# energy_counter_rfm70.net
KiCad netlist of a schematic drawn in EAGLE
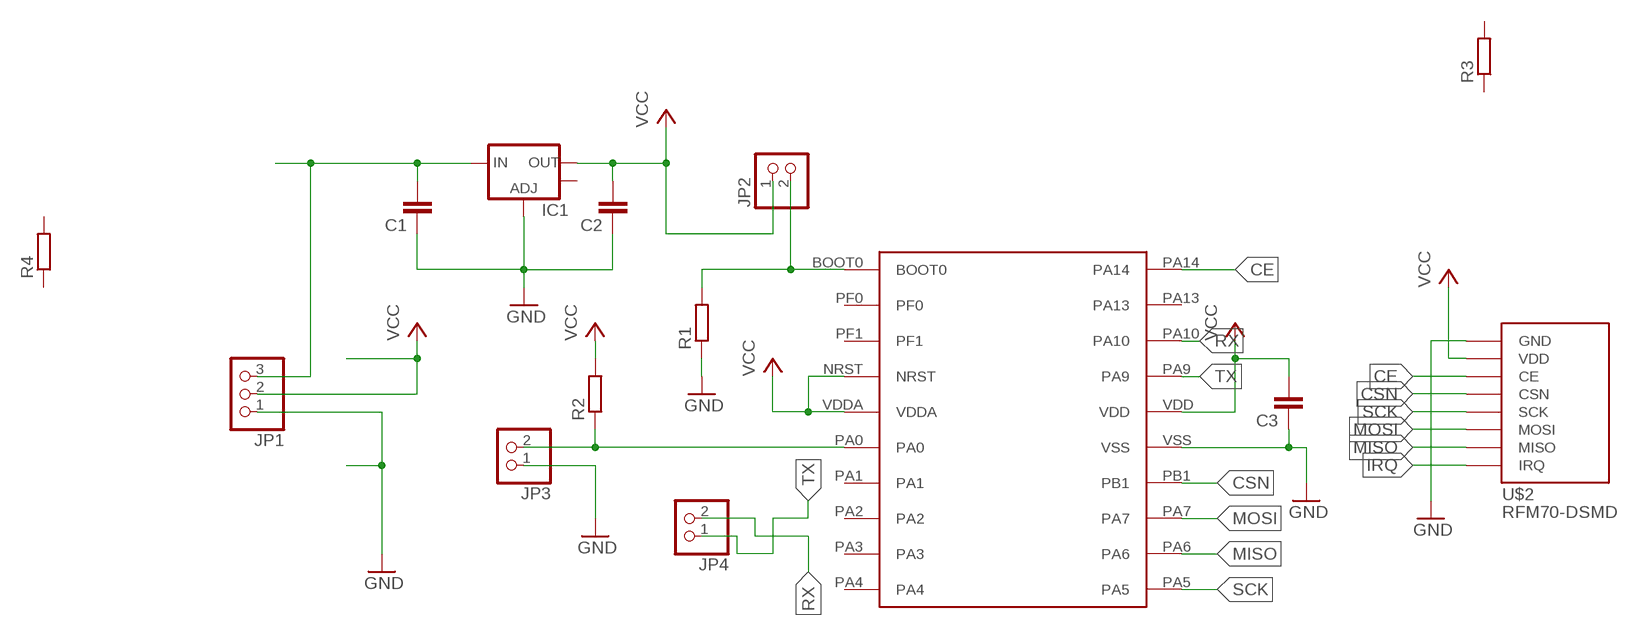
[diagram p0: schematic, sheet 1]

(export (version "E")
  (design (tool "Eeschema 10.0.6"))
  (components
    (comp (ref "C1")
      (value "C-EUC1206")
      (footprint "eagle-import:C1206")
      (libsource (lib "eagle-import") (part "C-EUC1206"))
    )
    (comp (ref "C2")
      (value "C-EUC0805")
      (footprint "eagle-import:C0805")
      (libsource (lib "eagle-import") (part "C-EUC0805"))
    )
    (comp (ref "C3")
      (value "C-EUC0805")
      (footprint "eagle-import:C0805")
      (libsource (lib "eagle-import") (part "C-EUC0805"))
    )
    (comp (ref "IC1")
      (value "V_REG_LM1117SOT223")
      (footprint "eagle-import:SOT223")
      (libsource (lib "eagle-import") (part "V_REG_LM1117SOT223"))
    )
    (comp (ref "JP1")
      (value "PINHD-1X3/90")
      (footprint "eagle-import:1X03_90")
      (libsource (lib "eagle-import") (part "PINHD-1X3/90"))
    )
    (comp (ref "JP2")
      (value "PINHD-1X2/90")
      (footprint "eagle-import:1X02_90")
      (libsource (lib "eagle-import") (part "PINHD-1X2/90"))
    )
    (comp (ref "JP3")
      (value "PINHD-1X2/90")
      (footprint "eagle-import:1X02_90")
      (libsource (lib "eagle-import") (part "PINHD-1X2/90"))
    )
    (comp (ref "JP4")
      (value "PINHD-1X2/90")
      (footprint "eagle-import:1X02_90")
      (libsource (lib "eagle-import") (part "PINHD-1X2/90"))
    )
    (comp (ref "R1")
      (value "R-EU_R1206")
      (footprint "eagle-import:R1206")
      (libsource (lib "eagle-import") (part "R-EU_R1206"))
    )
    (comp (ref "R2")
      (value "R-EU_R0805")
      (footprint "eagle-import:R0805")
      (libsource (lib "eagle-import") (part "R-EU_R0805"))
    )
    (comp (ref "R3")
      (value "R-EU_R1206")
      (footprint "eagle-import:R1206")
      (libsource (lib "eagle-import") (part "R-EU_R1206"))
    )
    (comp (ref "R4")
      (value "R-EU_R1206")
      (footprint "eagle-import:R1206")
      (libsource (lib "eagle-import") (part "R-EU_R1206"))
    )
    (comp (ref "U$1")
      (value "STM32F0")
      (footprint "eagle-import:TSSOP20")
      (libsource (lib "eagle-import") (part "STM32F0"))
    )
    (comp (ref "U$2")
      (value "RFM70-DSMD")
      (footprint "eagle-import:RFM70-SMD")
      (libsource (lib "eagle-import") (part "RFM70-DSMD"))
    )
  )
  (nets
    (net (code "1") (name "CE") (class "Default")
      (node (ref "U$1") (pin "PA14") (pinfunction "PA14_PA14") (pintype "bidirectional"))
      (node (ref "U$2") (pin "CE") (pinfunction "CE_CE") (pintype "bidirectional"))
    )
    (net (code "2") (name "CSN") (class "Default")
      (node (ref "U$1") (pin "PB1") (pinfunction "PB1_PB1") (pintype "bidirectional"))
      (node (ref "U$2") (pin "CSN") (pinfunction "CSN_CSN") (pintype "bidirectional"))
    )
    (net (code "3") (name "GND") (class "Default")
      (node (ref "C1") (pin "1") (pinfunction "1_1") (pintype "passive"))
      (node (ref "C2") (pin "1") (pinfunction "1_1") (pintype "passive"))
      (node (ref "C3") (pin "1") (pinfunction "1_1") (pintype "passive"))
      (node (ref "IC1") (pin "1") (pinfunction "ADJ_1") (pintype "input"))
      (node (ref "JP1") (pin "1") (pinfunction "1_1") (pintype "passive"))
      (node (ref "JP3") (pin "1") (pinfunction "1_1") (pintype "passive"))
      (node (ref "R1") (pin "1") (pinfunction "1_1") (pintype "passive"))
      (node (ref "U$1") (pin "VSS") (pinfunction "VSS_VSS") (pintype "bidirectional"))
      (node (ref "U$2") (pin "GND") (pinfunction "GND_GND") (pintype "bidirectional"))
    )
    (net (code "4") (name "IRQ") (class "Default")
      (node (ref "U$2") (pin "IRQ") (pinfunction "IRQ_IRQ") (pintype "bidirectional"))
    )
    (net (code "5") (name "MISO") (class "Default")
      (node (ref "U$1") (pin "PA6") (pinfunction "PA6_PA6") (pintype "bidirectional"))
      (node (ref "U$2") (pin "MISO") (pinfunction "MISO_MISO") (pintype "bidirectional"))
    )
    (net (code "6") (name "MOSI") (class "Default")
      (node (ref "U$1") (pin "PA7") (pinfunction "PA7_PA7") (pintype "bidirectional"))
      (node (ref "U$2") (pin "MOSI") (pinfunction "MOSI_MOSI") (pintype "bidirectional"))
    )
    (net (code "7") (name "Net-(IC1-IN)") (class "Default")
      (node (ref "C1") (pin "2") (pinfunction "2_2") (pintype "passive"))
      (node (ref "IC1") (pin "3") (pinfunction "IN_3") (pintype "input"))
      (node (ref "JP1") (pin "3") (pinfunction "3_3") (pintype "passive"))
    )
    (net (code "8") (name "Net-(JP2-Pad2)") (class "Default")
      (node (ref "JP2") (pin "2") (pinfunction "2_2") (pintype "passive"))
      (node (ref "R1") (pin "2") (pinfunction "2_2") (pintype "passive"))
      (node (ref "U$1") (pin "BOOT0") (pinfunction "BOOT0_BOOT0") (pintype "bidirectional"))
    )
    (net (code "9") (name "Net-(JP3-Pad2)") (class "Default")
      (node (ref "JP3") (pin "2") (pinfunction "2_2") (pintype "passive"))
      (node (ref "R2") (pin "1") (pinfunction "1_1") (pintype "passive"))
      (node (ref "U$1") (pin "PA0") (pinfunction "PA0_PA0") (pintype "bidirectional"))
    )
    (net (code "10") (name "RX") (class "Default")
      (node (ref "JP4") (pin "2") (pinfunction "2_2") (pintype "passive"))
      (node (ref "U$1") (pin "PA10") (pinfunction "PA10_PA10") (pintype "bidirectional"))
    )
    (net (code "11") (name "SCK") (class "Default")
      (node (ref "U$1") (pin "PA5") (pinfunction "PA5_PA5") (pintype "bidirectional"))
      (node (ref "U$2") (pin "SCK") (pinfunction "SCK_SCK") (pintype "bidirectional"))
    )
    (net (code "12") (name "TX") (class "Default")
      (node (ref "JP4") (pin "1") (pinfunction "1_1") (pintype "passive"))
      (node (ref "U$1") (pin "PA9") (pinfunction "PA9_PA9") (pintype "bidirectional"))
    )
    (net (code "13") (name "VCC") (class "Default")
      (node (ref "C2") (pin "2") (pinfunction "2_2") (pintype "passive"))
      (node (ref "C3") (pin "2") (pinfunction "2_2") (pintype "passive"))
      (node (ref "IC1") (pin "2") (pinfunction "OUT_2") (pintype "output"))
      (node (ref "JP1") (pin "2") (pinfunction "2_2") (pintype "passive"))
      (node (ref "JP2") (pin "1") (pinfunction "1_1") (pintype "passive"))
      (node (ref "R2") (pin "2") (pinfunction "2_2") (pintype "passive"))
      (node (ref "U$1") (pin "NRST") (pinfunction "NRST_NRST") (pintype "bidirectional"))
      (node (ref "U$1") (pin "VDD") (pinfunction "VDD_VDD") (pintype "bidirectional"))
      (node (ref "U$1") (pin "VDDA") (pinfunction "VDDA_VDDA") (pintype "bidirectional"))
      (node (ref "U$2") (pin "VDD") (pinfunction "VDD_VDD") (pintype "bidirectional"))
    )
    (net (code "14") (name "unconnected-(IC1-OUT-Pad4)") (class "Default")
      (node (ref "IC1") (pin "4") (pinfunction "OUT_4") (pintype "output"))
    )
    (net (code "15") (name "unconnected-(R3-Pad1)") (class "Default")
      (node (ref "R3") (pin "1") (pinfunction "1_1") (pintype "passive"))
    )
    (net (code "16") (name "unconnected-(R3-Pad2)") (class "Default")
      (node (ref "R3") (pin "2") (pinfunction "2_2") (pintype "passive"))
    )
    (net (code "17") (name "unconnected-(R4-Pad1)") (class "Default")
      (node (ref "R4") (pin "1") (pinfunction "1_1") (pintype "passive"))
    )
    (net (code "18") (name "unconnected-(R4-Pad2)") (class "Default")
      (node (ref "R4") (pin "2") (pinfunction "2_2") (pintype "passive"))
    )
    (net (code "19") (name "unconnected-(U$1-PadPA1)") (class "Default")
      (node (ref "U$1") (pin "PA1") (pinfunction "PA1_PA1") (pintype "bidirectional"))
    )
    (net (code "20") (name "unconnected-(U$1-PadPA2)") (class "Default")
      (node (ref "U$1") (pin "PA2") (pinfunction "PA2_PA2") (pintype "bidirectional"))
    )
    (net (code "21") (name "unconnected-(U$1-PadPA3)") (class "Default")
      (node (ref "U$1") (pin "PA3") (pinfunction "PA3_PA3") (pintype "bidirectional"))
    )
    (net (code "22") (name "unconnected-(U$1-PadPA4)") (class "Default")
      (node (ref "U$1") (pin "PA4") (pinfunction "PA4_PA4") (pintype "bidirectional"))
    )
    (net (code "23") (name "unconnected-(U$1-PadPA13)") (class "Default")
      (node (ref "U$1") (pin "PA13") (pinfunction "PA13_PA13") (pintype "bidirectional"))
    )
    (net (code "24") (name "unconnected-(U$1-PadPF0)") (class "Default")
      (node (ref "U$1") (pin "PF0") (pinfunction "PF0_PF0") (pintype "bidirectional"))
    )
    (net (code "25") (name "unconnected-(U$1-PadPF1)") (class "Default")
      (node (ref "U$1") (pin "PF1") (pinfunction "PF1_PF1") (pintype "bidirectional"))
    )
  )
)
